# STM32.net
KiCad netlist of a schematic drawn in Altium Designer
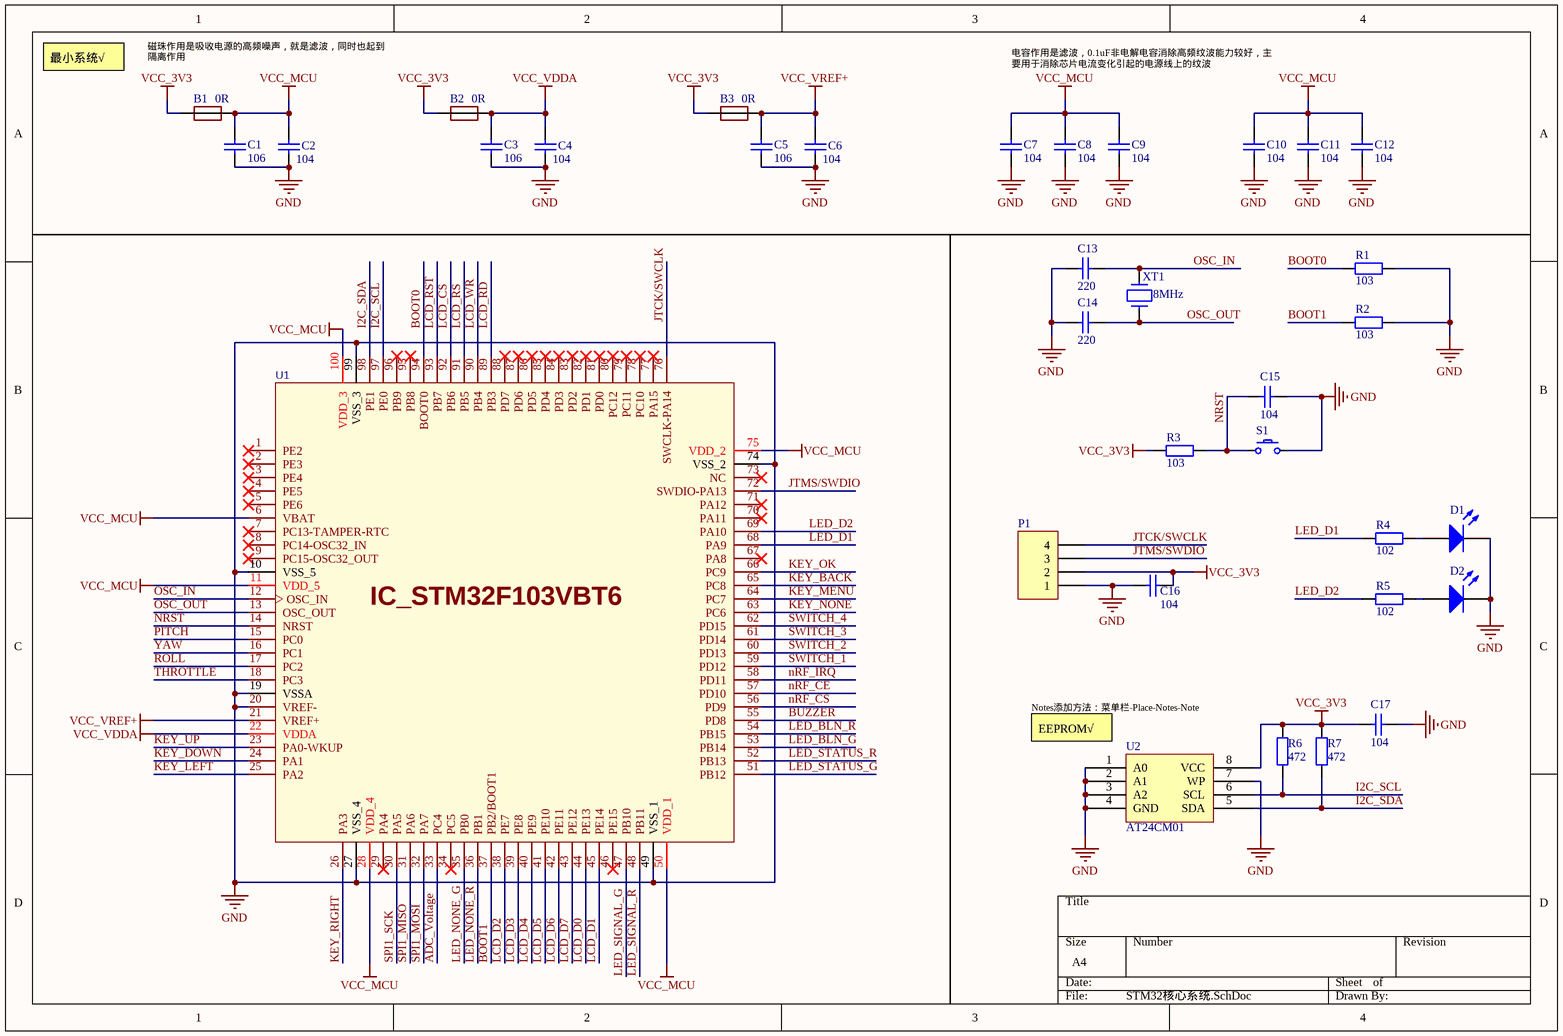
[diagram p0: STM32核心系统.SchDoc]

(export (version "E")
  (design (tool "Eeschema 10.0.6"))
  (components
    (comp (ref "B1")
      (value "0R")
      (footprint "CC1608-0603")
      (description "磁珠")
      (fields (field (name "Comment") "MPZ1608S101ATDH5"))
      (libsource (lib "SCHLIB") (part "FB_BEAD"))
    )
    (comp (ref "B2")
      (value "0R")
      (footprint "CC1608-0603")
      (description "磁珠")
      (fields (field (name "Comment") "MPZ1608S101ATDH5"))
      (libsource (lib "SCHLIB") (part "FB_BEAD"))
    )
    (comp (ref "B3")
      (value "0R")
      (footprint "CC1608-0603")
      (description "磁珠")
      (fields (field (name "Comment") "MPZ1608S101ATDH5"))
      (libsource (lib "SCHLIB") (part "FB_BEAD"))
    )
    (comp (ref "C1")
      (value "106")
      (footprint "CC1608-0603")
      (description "Capacitor")
      (fields (field (name "Comment") "Cap") (field (name "PUBLISHER") "Altium Limited"))
      (libsource (lib "Miscellaneous Devices") (part "Cap"))
    )
    (comp (ref "C2")
      (value "104")
      (footprint "CC1608-0603")
      (description "Capacitor")
      (fields (field (name "Comment") "Cap") (field (name "PUBLISHER") "Altium Limited"))
      (libsource (lib "Miscellaneous Devices") (part "Cap"))
    )
    (comp (ref "C3")
      (value "106")
      (footprint "CC1608-0603")
      (description "Capacitor")
      (fields (field (name "Comment") "Cap") (field (name "PUBLISHER") "Altium Limited"))
      (libsource (lib "Miscellaneous Devices") (part "Cap"))
    )
    (comp (ref "C4")
      (value "104")
      (footprint "CC1608-0603")
      (description "Capacitor")
      (fields (field (name "Comment") "Cap") (field (name "PUBLISHER") "Altium Limited"))
      (libsource (lib "Miscellaneous Devices") (part "Cap"))
    )
    (comp (ref "C5")
      (value "106")
      (footprint "CC1608-0603")
      (description "Capacitor")
      (fields (field (name "Comment") "Cap") (field (name "PUBLISHER") "Altium Limited"))
      (libsource (lib "Miscellaneous Devices") (part "Cap"))
    )
    (comp (ref "C6")
      (value "104")
      (footprint "CC1608-0603")
      (description "Capacitor")
      (fields (field (name "Comment") "Cap") (field (name "PUBLISHER") "Altium Limited"))
      (libsource (lib "Miscellaneous Devices") (part "Cap"))
    )
    (comp (ref "C7")
      (value "104")
      (footprint "CC1608-0603")
      (description "Capacitor")
      (fields (field (name "Comment") "Cap") (field (name "PUBLISHER") "Altium Limited"))
      (libsource (lib "Miscellaneous Devices") (part "Cap"))
    )
    (comp (ref "C8")
      (value "104")
      (footprint "CC1608-0603")
      (description "Capacitor")
      (fields (field (name "Comment") "Cap") (field (name "PUBLISHER") "Altium Limited"))
      (libsource (lib "Miscellaneous Devices") (part "Cap"))
    )
    (comp (ref "C9")
      (value "104")
      (footprint "CC1608-0603")
      (description "Capacitor")
      (fields (field (name "Comment") "Cap") (field (name "PUBLISHER") "Altium Limited"))
      (libsource (lib "Miscellaneous Devices") (part "Cap"))
    )
    (comp (ref "C10")
      (value "104")
      (footprint "CC1608-0603")
      (description "Capacitor")
      (fields (field (name "Comment") "Cap") (field (name "PUBLISHER") "Altium Limited"))
      (libsource (lib "Miscellaneous Devices") (part "Cap"))
    )
    (comp (ref "C11")
      (value "104")
      (footprint "CC1608-0603")
      (description "Capacitor")
      (fields (field (name "Comment") "Cap") (field (name "PUBLISHER") "Altium Limited"))
      (libsource (lib "Miscellaneous Devices") (part "Cap"))
    )
    (comp (ref "C12")
      (value "104")
      (footprint "CC1608-0603")
      (description "Capacitor")
      (fields (field (name "Comment") "Cap") (field (name "PUBLISHER") "Altium Limited"))
      (libsource (lib "Miscellaneous Devices") (part "Cap"))
    )
    (comp (ref "C13")
      (value "220")
      (footprint "CC1608-0603")
      (description "Capacitor")
      (fields (field (name "Comment") "Cap") (field (name "PUBLISHER") "Altium Limited"))
      (libsource (lib "Miscellaneous Devices") (part "Cap"))
    )
    (comp (ref "C14")
      (value "220")
      (footprint "CC1608-0603")
      (description "Capacitor")
      (fields (field (name "Comment") "Cap") (field (name "PUBLISHER") "Altium Limited"))
      (libsource (lib "Miscellaneous Devices") (part "Cap"))
    )
    (comp (ref "C15")
      (value "104")
      (footprint "CC1608-0603")
      (description "Capacitor")
      (fields (field (name "Comment") "Cap") (field (name "PUBLISHER") "Altium Limited"))
      (libsource (lib "Miscellaneous Devices") (part "Cap"))
    )
    (comp (ref "C16")
      (value "104")
      (footprint "CC1608-0603")
      (description "Capacitor")
      (fields (field (name "Comment") "Cap") (field (name "PUBLISHER") "Altium Limited"))
      (libsource (lib "Miscellaneous Devices") (part "Cap"))
    )
    (comp (ref "C17")
      (value "104")
      (footprint "CC1608-0603")
      (description "Capacitor")
      (fields (field (name "Comment") "Cap") (field (name "PUBLISHER") "Altium Limited"))
      (libsource (lib "Miscellaneous Devices") (part "Cap"))
    )
    (comp (ref "D1")
      (value "LED0")
      (footprint "CD1608-0603")
      (description "Typical INFRARED GaAs LED")
      (fields (field (name "PUBLISHER") "Altium Limited"))
      (libsource (lib "Miscellaneous Devices") (part "LED0"))
    )
    (comp (ref "D2")
      (value "LED0")
      (footprint "CD1608-0603")
      (description "Typical INFRARED GaAs LED")
      (fields (field (name "PUBLISHER") "Altium Limited"))
      (libsource (lib "Miscellaneous Devices") (part "LED0"))
    )
    (comp (ref "P1")
      (value "Header 4")
      (footprint "XHT4-2.54")
      (description "Header, 4-Pin")
      (fields (field (name "PUBLISHER") "Altium Limited"))
      (libsource (lib "Miscellaneous Connectors") (part "Header 4"))
    )
    (comp (ref "R1")
      (value "103")
      (footprint "CC1608-0603")
      (description "电阻")
      (fields (field (name "Comment") "RX_RES"))
      (libsource (lib "") (part "RX_RES_1"))
    )
    (comp (ref "R2")
      (value "103")
      (footprint "CC1608-0603")
      (description "电阻")
      (fields (field (name "Comment") "RX_RES"))
      (libsource (lib "") (part "RX_RES_1"))
    )
    (comp (ref "R3")
      (value "103")
      (footprint "CC1608-0603")
      (description "电阻")
      (fields (field (name "Comment") "RX_RES"))
      (libsource (lib "") (part "RX_RES_1"))
    )
    (comp (ref "R4")
      (value "102")
      (footprint "CC1608-0603")
      (description "电阻")
      (fields (field (name "Comment") "RX_RES"))
      (libsource (lib "") (part "RX_RES_1"))
    )
    (comp (ref "R5")
      (value "102")
      (footprint "CC1608-0603")
      (description "电阻")
      (fields (field (name "Comment") "RX_RES"))
      (libsource (lib "") (part "RX_RES_1"))
    )
    (comp (ref "R6")
      (value "472")
      (footprint "CC1608-0603")
      (description "电阻")
      (fields (field (name "Comment") "RX_RES"))
      (libsource (lib "SCHLIB") (part "RX_RES"))
    )
    (comp (ref "R7")
      (value "472")
      (footprint "CC1608-0603")
      (description "电阻")
      (fields (field (name "Comment") "RX_RES"))
      (libsource (lib "SCHLIB") (part "RX_RES"))
    )
    (comp (ref "S1")
      (value "KG_SW-PB-2")
      (footprint "L7.3X7.3X3.2")
      (description "2脚开关")
      (libsource (lib "SCHLIB") (part "KG_SW-PB-2"))
    )
    (comp (ref "U1")
      (value "IC_STM32F103VBT6")
      (footprint "LQFP-100_L14.0-W14.0-P0.50-LS16.0-BL")
      (description "STM32单片机")
      (fields
        (field (name "BOM_SUPPLIER PART") "C8314")
        (field (name "BOM_MANUFACTURER PART") "STM32F103VBT6")
      )
      (libsource (lib "SCHLIB") (part "IC_STM32F103VBT6"))
    )
    (comp (ref "U2")
      (value "AT24CM01")
      (footprint "SO8")
      (description "存储芯片")
      (libsource (lib "SCHLIB") (part "IC_AT24C02"))
    )
    (comp (ref "XT1")
      (value "8MHz")
      (footprint "OSC2-SMD_L5.0-W3.2")
      (description "2P晶振")
      (fields (field (name "Comment") "XT_CRYSTAL2P"))
      (libsource (lib "SCHLIB") (part "XT_CRYSTAL2P"))
    )
  )
  (nets
    (net (code "1") (name "/ADC_Voltage") (class "Default")
      (node (ref "U1") (pin "33") (pinfunction "PC4_33") (pintype "passive"))
    )
    (net (code "2") (name "/BOOT0") (class "Default")
      (node (ref "R1") (pin "1") (pinfunction "1_1") (pintype "passive"))
      (node (ref "U1") (pin "94") (pinfunction "BOOT0_94") (pintype "passive"))
    )
    (net (code "3") (name "/BOOT1") (class "Default")
      (node (ref "R2") (pin "1") (pinfunction "1_1") (pintype "passive"))
      (node (ref "U1") (pin "37") (pinfunction "PB2/BOOT1_37") (pintype "passive"))
    )
    (net (code "4") (name "/BUZZER") (class "Default")
      (node (ref "U1") (pin "55") (pinfunction "PD8_55") (pintype "passive"))
    )
    (net (code "5") (name "/I2C_SCL") (class "Default")
      (node (ref "R6") (pin "1") (pinfunction "1_1") (pintype "passive"))
      (node (ref "U1") (pin "97") (pinfunction "PE0_97") (pintype "passive"))
      (node (ref "U2") (pin "6") (pinfunction "SCL_6") (pintype "passive"))
    )
    (net (code "6") (name "/I2C_SDA") (class "Default")
      (node (ref "R7") (pin "1") (pinfunction "1_1") (pintype "passive"))
      (node (ref "U1") (pin "98") (pinfunction "PE1_98") (pintype "passive"))
      (node (ref "U2") (pin "5") (pinfunction "SDA_5") (pintype "passive"))
    )
    (net (code "7") (name "/JTCK{slash}SWCLK") (class "Default")
      (node (ref "P1") (pin "4") (pinfunction "4_4") (pintype "passive"))
      (node (ref "U1") (pin "76") (pinfunction "SWCLK-PA14_76") (pintype "passive"))
    )
    (net (code "8") (name "/JTMS{slash}SWDIO") (class "Default")
      (node (ref "P1") (pin "3") (pinfunction "3_3") (pintype "passive"))
      (node (ref "U1") (pin "72") (pinfunction "SWDIO-PA13_72") (pintype "passive"))
    )
    (net (code "9") (name "/KEY_BACK") (class "Default")
      (node (ref "U1") (pin "65") (pinfunction "PC8_65") (pintype "passive"))
    )
    (net (code "10") (name "/KEY_DOWN") (class "Default")
      (node (ref "U1") (pin "24") (pinfunction "PA1_24") (pintype "passive"))
    )
    (net (code "11") (name "/KEY_LEFT") (class "Default")
      (node (ref "U1") (pin "25") (pinfunction "PA2_25") (pintype "passive"))
    )
    (net (code "12") (name "/KEY_MENU") (class "Default")
      (node (ref "U1") (pin "64") (pinfunction "PC7_64") (pintype "passive"))
    )
    (net (code "13") (name "/KEY_NONE") (class "Default")
      (node (ref "U1") (pin "63") (pinfunction "PC6_63") (pintype "passive"))
    )
    (net (code "14") (name "/KEY_OK") (class "Default")
      (node (ref "U1") (pin "66") (pinfunction "PC9_66") (pintype "passive"))
    )
    (net (code "15") (name "/KEY_RIGHT") (class "Default")
      (node (ref "U1") (pin "26") (pinfunction "PA3_26") (pintype "passive"))
    )
    (net (code "16") (name "/KEY_UP") (class "Default")
      (node (ref "U1") (pin "23") (pinfunction "PA0-WKUP_23") (pintype "passive"))
    )
    (net (code "17") (name "/LCD_CS") (class "Default")
      (node (ref "U1") (pin "92") (pinfunction "PB6_92") (pintype "passive"))
    )
    (net (code "18") (name "/LCD_D0") (class "Default")
      (node (ref "U1") (pin "44") (pinfunction "PE13_44") (pintype "passive"))
    )
    (net (code "19") (name "/LCD_D1") (class "Default")
      (node (ref "U1") (pin "45") (pinfunction "PE14_45") (pintype "passive"))
    )
    (net (code "20") (name "/LCD_D2") (class "Default")
      (node (ref "U1") (pin "38") (pinfunction "PE7_38") (pintype "passive"))
    )
    (net (code "21") (name "/LCD_D3") (class "Default")
      (node (ref "U1") (pin "39") (pinfunction "PE8_39") (pintype "passive"))
    )
    (net (code "22") (name "/LCD_D4") (class "Default")
      (node (ref "U1") (pin "40") (pinfunction "PE9_40") (pintype "passive"))
    )
    (net (code "23") (name "/LCD_D5") (class "Default")
      (node (ref "U1") (pin "41") (pinfunction "PE10_41") (pintype "passive"))
    )
    (net (code "24") (name "/LCD_D6") (class "Default")
      (node (ref "U1") (pin "42") (pinfunction "PE11_42") (pintype "passive"))
    )
    (net (code "25") (name "/LCD_D7") (class "Default")
      (node (ref "U1") (pin "43") (pinfunction "PE12_43") (pintype "passive"))
    )
    (net (code "26") (name "/LCD_RD") (class "Default")
      (node (ref "U1") (pin "89") (pinfunction "PB3_89") (pintype "passive"))
    )
    (net (code "27") (name "/LCD_RS") (class "Default")
      (node (ref "U1") (pin "91") (pinfunction "PB5_91") (pintype "passive"))
    )
    (net (code "28") (name "/LCD_RST") (class "Default")
      (node (ref "U1") (pin "93") (pinfunction "PB7_93") (pintype "passive"))
    )
    (net (code "29") (name "/LCD_WR") (class "Default")
      (node (ref "U1") (pin "90") (pinfunction "PB4_90") (pintype "passive"))
    )
    (net (code "30") (name "/LED_BLN_G") (class "Default")
      (node (ref "U1") (pin "53") (pinfunction "PB14_53") (pintype "passive"))
    )
    (net (code "31") (name "/LED_BLN_R") (class "Default")
      (node (ref "U1") (pin "54") (pinfunction "PB15_54") (pintype "passive"))
    )
    (net (code "32") (name "/LED_D1") (class "Default")
      (node (ref "R4") (pin "1") (pinfunction "1_1") (pintype "passive"))
      (node (ref "U1") (pin "68") (pinfunction "PA9_68") (pintype "passive"))
    )
    (net (code "33") (name "/LED_D2") (class "Default")
      (node (ref "R5") (pin "1") (pinfunction "1_1") (pintype "passive"))
      (node (ref "U1") (pin "69") (pinfunction "PA10_69") (pintype "passive"))
    )
    (net (code "34") (name "/LED_NONE_G") (class "Default")
      (node (ref "U1") (pin "35") (pinfunction "PB0_35") (pintype "passive"))
    )
    (net (code "35") (name "/LED_NONE_R") (class "Default")
      (node (ref "U1") (pin "36") (pinfunction "PB1_36") (pintype "passive"))
    )
    (net (code "36") (name "/LED_SIGNAL_G") (class "Default")
      (node (ref "U1") (pin "47") (pinfunction "PB10_47") (pintype "passive"))
    )
    (net (code "37") (name "/LED_SIGNAL_R") (class "Default")
      (node (ref "U1") (pin "48") (pinfunction "PB11_48") (pintype "passive"))
    )
    (net (code "38") (name "/LED_STATUS_G") (class "Default")
      (node (ref "U1") (pin "51") (pinfunction "PB12_51") (pintype "passive"))
    )
    (net (code "39") (name "/LED_STATUS_R") (class "Default")
      (node (ref "U1") (pin "52") (pinfunction "PB13_52") (pintype "passive"))
    )
    (net (code "40") (name "/NRST") (class "Default")
      (node (ref "C15") (pin "2") (pinfunction "2_2") (pintype "passive"))
      (node (ref "R3") (pin "2") (pinfunction "2_2") (pintype "passive"))
      (node (ref "S1") (pin "1") (pinfunction "1_1") (pintype "passive"))
      (node (ref "U1") (pin "14") (pinfunction "NRST_14") (pintype "passive"))
    )
    (net (code "41") (name "/OSC_IN") (class "Default")
      (node (ref "C13") (pin "1") (pinfunction "1_1") (pintype "passive"))
      (node (ref "U1") (pin "12") (pinfunction "OSC_IN_12") (pintype "passive"))
      (node (ref "XT1") (pin "2") (pinfunction "2_2") (pintype "passive"))
    )
    (net (code "42") (name "/OSC_OUT") (class "Default")
      (node (ref "C14") (pin "1") (pinfunction "1_1") (pintype "passive"))
      (node (ref "U1") (pin "13") (pinfunction "OSC_OUT_13") (pintype "passive"))
      (node (ref "XT1") (pin "1") (pinfunction "1_1") (pintype "passive"))
    )
    (net (code "43") (name "/PITCH") (class "Default")
      (node (ref "U1") (pin "15") (pinfunction "PC0_15") (pintype "passive"))
    )
    (net (code "44") (name "/ROLL") (class "Default")
      (node (ref "U1") (pin "17") (pinfunction "PC2_17") (pintype "passive"))
    )
    (net (code "45") (name "/SPI1_MISO") (class "Default")
      (node (ref "U1") (pin "31") (pinfunction "PA6_31") (pintype "passive"))
    )
    (net (code "46") (name "/SPI1_MOSI") (class "Default")
      (node (ref "U1") (pin "32") (pinfunction "PA7_32") (pintype "passive"))
    )
    (net (code "47") (name "/SPI1_SCK") (class "Default")
      (node (ref "U1") (pin "30") (pinfunction "PA5_30") (pintype "passive"))
    )
    (net (code "48") (name "/SWITCH_1") (class "Default")
      (node (ref "U1") (pin "59") (pinfunction "PD12_59") (pintype "passive"))
    )
    (net (code "49") (name "/SWITCH_2") (class "Default")
      (node (ref "U1") (pin "60") (pinfunction "PD13_60") (pintype "passive"))
    )
    (net (code "50") (name "/SWITCH_3") (class "Default")
      (node (ref "U1") (pin "61") (pinfunction "PD14_61") (pintype "passive"))
    )
    (net (code "51") (name "/SWITCH_4") (class "Default")
      (node (ref "U1") (pin "62") (pinfunction "PD15_62") (pintype "passive"))
    )
    (net (code "52") (name "/THROTTLE") (class "Default")
      (node (ref "U1") (pin "18") (pinfunction "PC3_18") (pintype "passive"))
    )
    (net (code "53") (name "/YAW") (class "Default")
      (node (ref "U1") (pin "16") (pinfunction "PC1_16") (pintype "passive"))
    )
    (net (code "54") (name "/nRF_CE") (class "Default")
      (node (ref "U1") (pin "57") (pinfunction "PD10_57") (pintype "passive"))
    )
    (net (code "55") (name "/nRF_CS") (class "Default")
      (node (ref "U1") (pin "56") (pinfunction "PD9_56") (pintype "passive"))
    )
    (net (code "56") (name "/nRF_IRQ") (class "Default")
      (node (ref "U1") (pin "58") (pinfunction "PD11_58") (pintype "passive"))
    )
    (net (code "57") (name "GND") (class "Default")
      (node (ref "C1") (pin "1") (pinfunction "1_1") (pintype "passive"))
      (node (ref "C10") (pin "1") (pinfunction "1_1") (pintype "passive"))
      (node (ref "C11") (pin "1") (pinfunction "1_1") (pintype "passive"))
      (node (ref "C12") (pin "1") (pinfunction "1_1") (pintype "passive"))
      (node (ref "C13") (pin "2") (pinfunction "2_2") (pintype "passive"))
      (node (ref "C14") (pin "2") (pinfunction "2_2") (pintype "passive"))
      (node (ref "C15") (pin "1") (pinfunction "1_1") (pintype "passive"))
      (node (ref "C16") (pin "1") (pinfunction "1_1") (pintype "passive"))
      (node (ref "C17") (pin "1") (pinfunction "1_1") (pintype "passive"))
      (node (ref "C2") (pin "1") (pinfunction "1_1") (pintype "passive"))
      (node (ref "C3") (pin "1") (pinfunction "1_1") (pintype "passive"))
      (node (ref "C4") (pin "1") (pinfunction "1_1") (pintype "passive"))
      (node (ref "C5") (pin "1") (pinfunction "1_1") (pintype "passive"))
      (node (ref "C6") (pin "1") (pinfunction "1_1") (pintype "passive"))
      (node (ref "C7") (pin "1") (pinfunction "1_1") (pintype "passive"))
      (node (ref "C8") (pin "1") (pinfunction "1_1") (pintype "passive"))
      (node (ref "C9") (pin "1") (pinfunction "1_1") (pintype "passive"))
      (node (ref "D1") (pin "2") (pinfunction "K_2") (pintype "passive"))
      (node (ref "D2") (pin "2") (pinfunction "K_2") (pintype "passive"))
      (node (ref "P1") (pin "1") (pinfunction "1_1") (pintype "passive"))
      (node (ref "R1") (pin "2") (pinfunction "2_2") (pintype "passive"))
      (node (ref "R2") (pin "2") (pinfunction "2_2") (pintype "passive"))
      (node (ref "S1") (pin "2") (pinfunction "2_2") (pintype "passive"))
      (node (ref "U1") (pin "10") (pinfunction "VSS_5_10") (pintype "passive"))
      (node (ref "U1") (pin "19") (pinfunction "VSSA_19") (pintype "passive"))
      (node (ref "U1") (pin "20") (pinfunction "VREF-_20") (pintype "passive"))
      (node (ref "U1") (pin "27") (pinfunction "VSS_4_27") (pintype "passive"))
      (node (ref "U1") (pin "49") (pinfunction "VSS_1_49") (pintype "passive"))
      (node (ref "U1") (pin "74") (pinfunction "VSS_2_74") (pintype "passive"))
      (node (ref "U1") (pin "99") (pinfunction "VSS_3_99") (pintype "passive"))
      (node (ref "U2") (pin "1") (pinfunction "A0_1") (pintype "passive"))
      (node (ref "U2") (pin "2") (pinfunction "A1_2") (pintype "passive"))
      (node (ref "U2") (pin "3") (pinfunction "A2_3") (pintype "passive"))
      (node (ref "U2") (pin "4") (pinfunction "GND_4") (pintype "passive"))
      (node (ref "U2") (pin "7") (pinfunction "WP_7") (pintype "passive"))
    )
    (net (code "58") (name "Net-(D1-A)") (class "Default")
      (node (ref "D1") (pin "1") (pinfunction "A_1") (pintype "passive"))
      (node (ref "R4") (pin "2") (pinfunction "2_2") (pintype "passive"))
    )
    (net (code "59") (name "Net-(D2-A)") (class "Default")
      (node (ref "D2") (pin "1") (pinfunction "A_1") (pintype "passive"))
      (node (ref "R5") (pin "2") (pinfunction "2_2") (pintype "passive"))
    )
    (net (code "60") (name "VCC_3V3") (class "Default")
      (node (ref "B1") (pin "1") (pinfunction "1_1") (pintype "passive"))
      (node (ref "B2") (pin "1") (pinfunction "1_1") (pintype "passive"))
      (node (ref "B3") (pin "1") (pinfunction "1_1") (pintype "passive"))
      (node (ref "C16") (pin "2") (pinfunction "2_2") (pintype "passive"))
      (node (ref "C17") (pin "2") (pinfunction "2_2") (pintype "passive"))
      (node (ref "P1") (pin "2") (pinfunction "2_2") (pintype "passive"))
      (node (ref "R3") (pin "1") (pinfunction "1_1") (pintype "passive"))
      (node (ref "R6") (pin "2") (pinfunction "2_2") (pintype "passive"))
      (node (ref "R7") (pin "2") (pinfunction "2_2") (pintype "passive"))
      (node (ref "U2") (pin "8") (pinfunction "VCC_8") (pintype "passive"))
    )
    (net (code "61") (name "VCC_MCU") (class "Default")
      (node (ref "B1") (pin "2") (pinfunction "2_2") (pintype "passive"))
      (node (ref "C1") (pin "2") (pinfunction "2_2") (pintype "passive"))
      (node (ref "C10") (pin "2") (pinfunction "2_2") (pintype "passive"))
      (node (ref "C11") (pin "2") (pinfunction "2_2") (pintype "passive"))
      (node (ref "C12") (pin "2") (pinfunction "2_2") (pintype "passive"))
      (node (ref "C2") (pin "2") (pinfunction "2_2") (pintype "passive"))
      (node (ref "C7") (pin "2") (pinfunction "2_2") (pintype "passive"))
      (node (ref "C8") (pin "2") (pinfunction "2_2") (pintype "passive"))
      (node (ref "C9") (pin "2") (pinfunction "2_2") (pintype "passive"))
      (node (ref "U1") (pin "100") (pinfunction "VDD_3_100") (pintype "passive"))
      (node (ref "U1") (pin "11") (pinfunction "VDD_5_11") (pintype "passive"))
      (node (ref "U1") (pin "28") (pinfunction "VDD_4_28") (pintype "passive"))
      (node (ref "U1") (pin "50") (pinfunction "VDD_1_50") (pintype "passive"))
      (node (ref "U1") (pin "6") (pinfunction "VBAT_6") (pintype "passive"))
      (node (ref "U1") (pin "75") (pinfunction "VDD_2_75") (pintype "passive"))
    )
    (net (code "62") (name "VCC_VDDA") (class "Default")
      (node (ref "B2") (pin "2") (pinfunction "2_2") (pintype "passive"))
      (node (ref "C3") (pin "2") (pinfunction "2_2") (pintype "passive"))
      (node (ref "C4") (pin "2") (pinfunction "2_2") (pintype "passive"))
      (node (ref "U1") (pin "22") (pinfunction "VDDA_22") (pintype "passive"))
    )
    (net (code "63") (name "VCC_VREF+") (class "Default")
      (node (ref "B3") (pin "2") (pinfunction "2_2") (pintype "passive"))
      (node (ref "C5") (pin "2") (pinfunction "2_2") (pintype "passive"))
      (node (ref "C6") (pin "2") (pinfunction "2_2") (pintype "passive"))
      (node (ref "U1") (pin "21") (pinfunction "VREF+_21") (pintype "passive"))
    )
    (net (code "64") (name "unconnected-(U1-NC-Pad73)") (class "Default")
      (node (ref "U1") (pin "73") (pinfunction "NC_73") (pintype "passive+no_connect"))
    )
    (net (code "65") (name "unconnected-(U1-PA4-Pad29)") (class "Default")
      (node (ref "U1") (pin "29") (pinfunction "PA4_29") (pintype "passive+no_connect"))
    )
    (net (code "66") (name "unconnected-(U1-PA8-Pad67)") (class "Default")
      (node (ref "U1") (pin "67") (pinfunction "PA8_67") (pintype "passive+no_connect"))
    )
    (net (code "67") (name "unconnected-(U1-PA11-Pad70)") (class "Default")
      (node (ref "U1") (pin "70") (pinfunction "PA11_70") (pintype "passive+no_connect"))
    )
    (net (code "68") (name "unconnected-(U1-PA12-Pad71)") (class "Default")
      (node (ref "U1") (pin "71") (pinfunction "PA12_71") (pintype "passive+no_connect"))
    )
    (net (code "69") (name "unconnected-(U1-PA15-Pad77)") (class "Default")
      (node (ref "U1") (pin "77") (pinfunction "PA15_77") (pintype "passive+no_connect"))
    )
    (net (code "70") (name "unconnected-(U1-PB8-Pad95)") (class "Default")
      (node (ref "U1") (pin "95") (pinfunction "PB8_95") (pintype "passive+no_connect"))
    )
    (net (code "71") (name "unconnected-(U1-PB9-Pad96)") (class "Default")
      (node (ref "U1") (pin "96") (pinfunction "PB9_96") (pintype "passive+no_connect"))
    )
    (net (code "72") (name "unconnected-(U1-PC5-Pad34)") (class "Default")
      (node (ref "U1") (pin "34") (pinfunction "PC5_34") (pintype "passive+no_connect"))
    )
    (net (code "73") (name "unconnected-(U1-PC10-Pad78)") (class "Default")
      (node (ref "U1") (pin "78") (pinfunction "PC10_78") (pintype "passive+no_connect"))
    )
    (net (code "74") (name "unconnected-(U1-PC11-Pad79)") (class "Default")
      (node (ref "U1") (pin "79") (pinfunction "PC11_79") (pintype "passive+no_connect"))
    )
    (net (code "75") (name "unconnected-(U1-PC12-Pad80)") (class "Default")
      (node (ref "U1") (pin "80") (pinfunction "PC12_80") (pintype "passive+no_connect"))
    )
    (net (code "76") (name "unconnected-(U1-PC13-TAMPER-RTC-Pad7)") (class "Default")
      (node (ref "U1") (pin "7") (pinfunction "PC13-TAMPER-RTC_7") (pintype "passive+no_connect"))
    )
    (net (code "77") (name "unconnected-(U1-PC14-OSC32_IN-Pad8)") (class "Default")
      (node (ref "U1") (pin "8") (pinfunction "PC14-OSC32_IN_8") (pintype "passive+no_connect"))
    )
    (net (code "78") (name "unconnected-(U1-PC15-OSC32_OUT-Pad9)") (class "Default")
      (node (ref "U1") (pin "9") (pinfunction "PC15-OSC32_OUT_9") (pintype "passive+no_connect"))
    )
    (net (code "79") (name "unconnected-(U1-PD0-Pad81)") (class "Default")
      (node (ref "U1") (pin "81") (pinfunction "PD0_81") (pintype "passive+no_connect"))
    )
    (net (code "80") (name "unconnected-(U1-PD1-Pad82)") (class "Default")
      (node (ref "U1") (pin "82") (pinfunction "PD1_82") (pintype "passive+no_connect"))
    )
    (net (code "81") (name "unconnected-(U1-PD2-Pad83)") (class "Default")
      (node (ref "U1") (pin "83") (pinfunction "PD2_83") (pintype "passive+no_connect"))
    )
    (net (code "82") (name "unconnected-(U1-PD3-Pad84)") (class "Default")
      (node (ref "U1") (pin "84") (pinfunction "PD3_84") (pintype "passive+no_connect"))
    )
    (net (code "83") (name "unconnected-(U1-PD4-Pad85)") (class "Default")
      (node (ref "U1") (pin "85") (pinfunction "PD4_85") (pintype "passive+no_connect"))
    )
    (net (code "84") (name "unconnected-(U1-PD5-Pad86)") (class "Default")
      (node (ref "U1") (pin "86") (pinfunction "PD5_86") (pintype "passive+no_connect"))
    )
    (net (code "85") (name "unconnected-(U1-PD6-Pad87)") (class "Default")
      (node (ref "U1") (pin "87") (pinfunction "PD6_87") (pintype "passive+no_connect"))
    )
    (net (code "86") (name "unconnected-(U1-PD7-Pad88)") (class "Default")
      (node (ref "U1") (pin "88") (pinfunction "PD7_88") (pintype "passive+no_connect"))
    )
    (net (code "87") (name "unconnected-(U1-PE2-Pad1)") (class "Default")
      (node (ref "U1") (pin "1") (pinfunction "PE2_1") (pintype "passive+no_connect"))
    )
    (net (code "88") (name "unconnected-(U1-PE3-Pad2)") (class "Default")
      (node (ref "U1") (pin "2") (pinfunction "PE3_2") (pintype "passive+no_connect"))
    )
    (net (code "89") (name "unconnected-(U1-PE4-Pad3)") (class "Default")
      (node (ref "U1") (pin "3") (pinfunction "PE4_3") (pintype "passive+no_connect"))
    )
    (net (code "90") (name "unconnected-(U1-PE5-Pad4)") (class "Default")
      (node (ref "U1") (pin "4") (pinfunction "PE5_4") (pintype "passive+no_connect"))
    )
    (net (code "91") (name "unconnected-(U1-PE6-Pad5)") (class "Default")
      (node (ref "U1") (pin "5") (pinfunction "PE6_5") (pintype "passive+no_connect"))
    )
    (net (code "92") (name "unconnected-(U1-PE15-Pad46)") (class "Default")
      (node (ref "U1") (pin "46") (pinfunction "PE15_46") (pintype "passive+no_connect"))
    )
  )
)
